# main_board.net
KiCad netlist of a schematic drawn in EasyEDA Pro
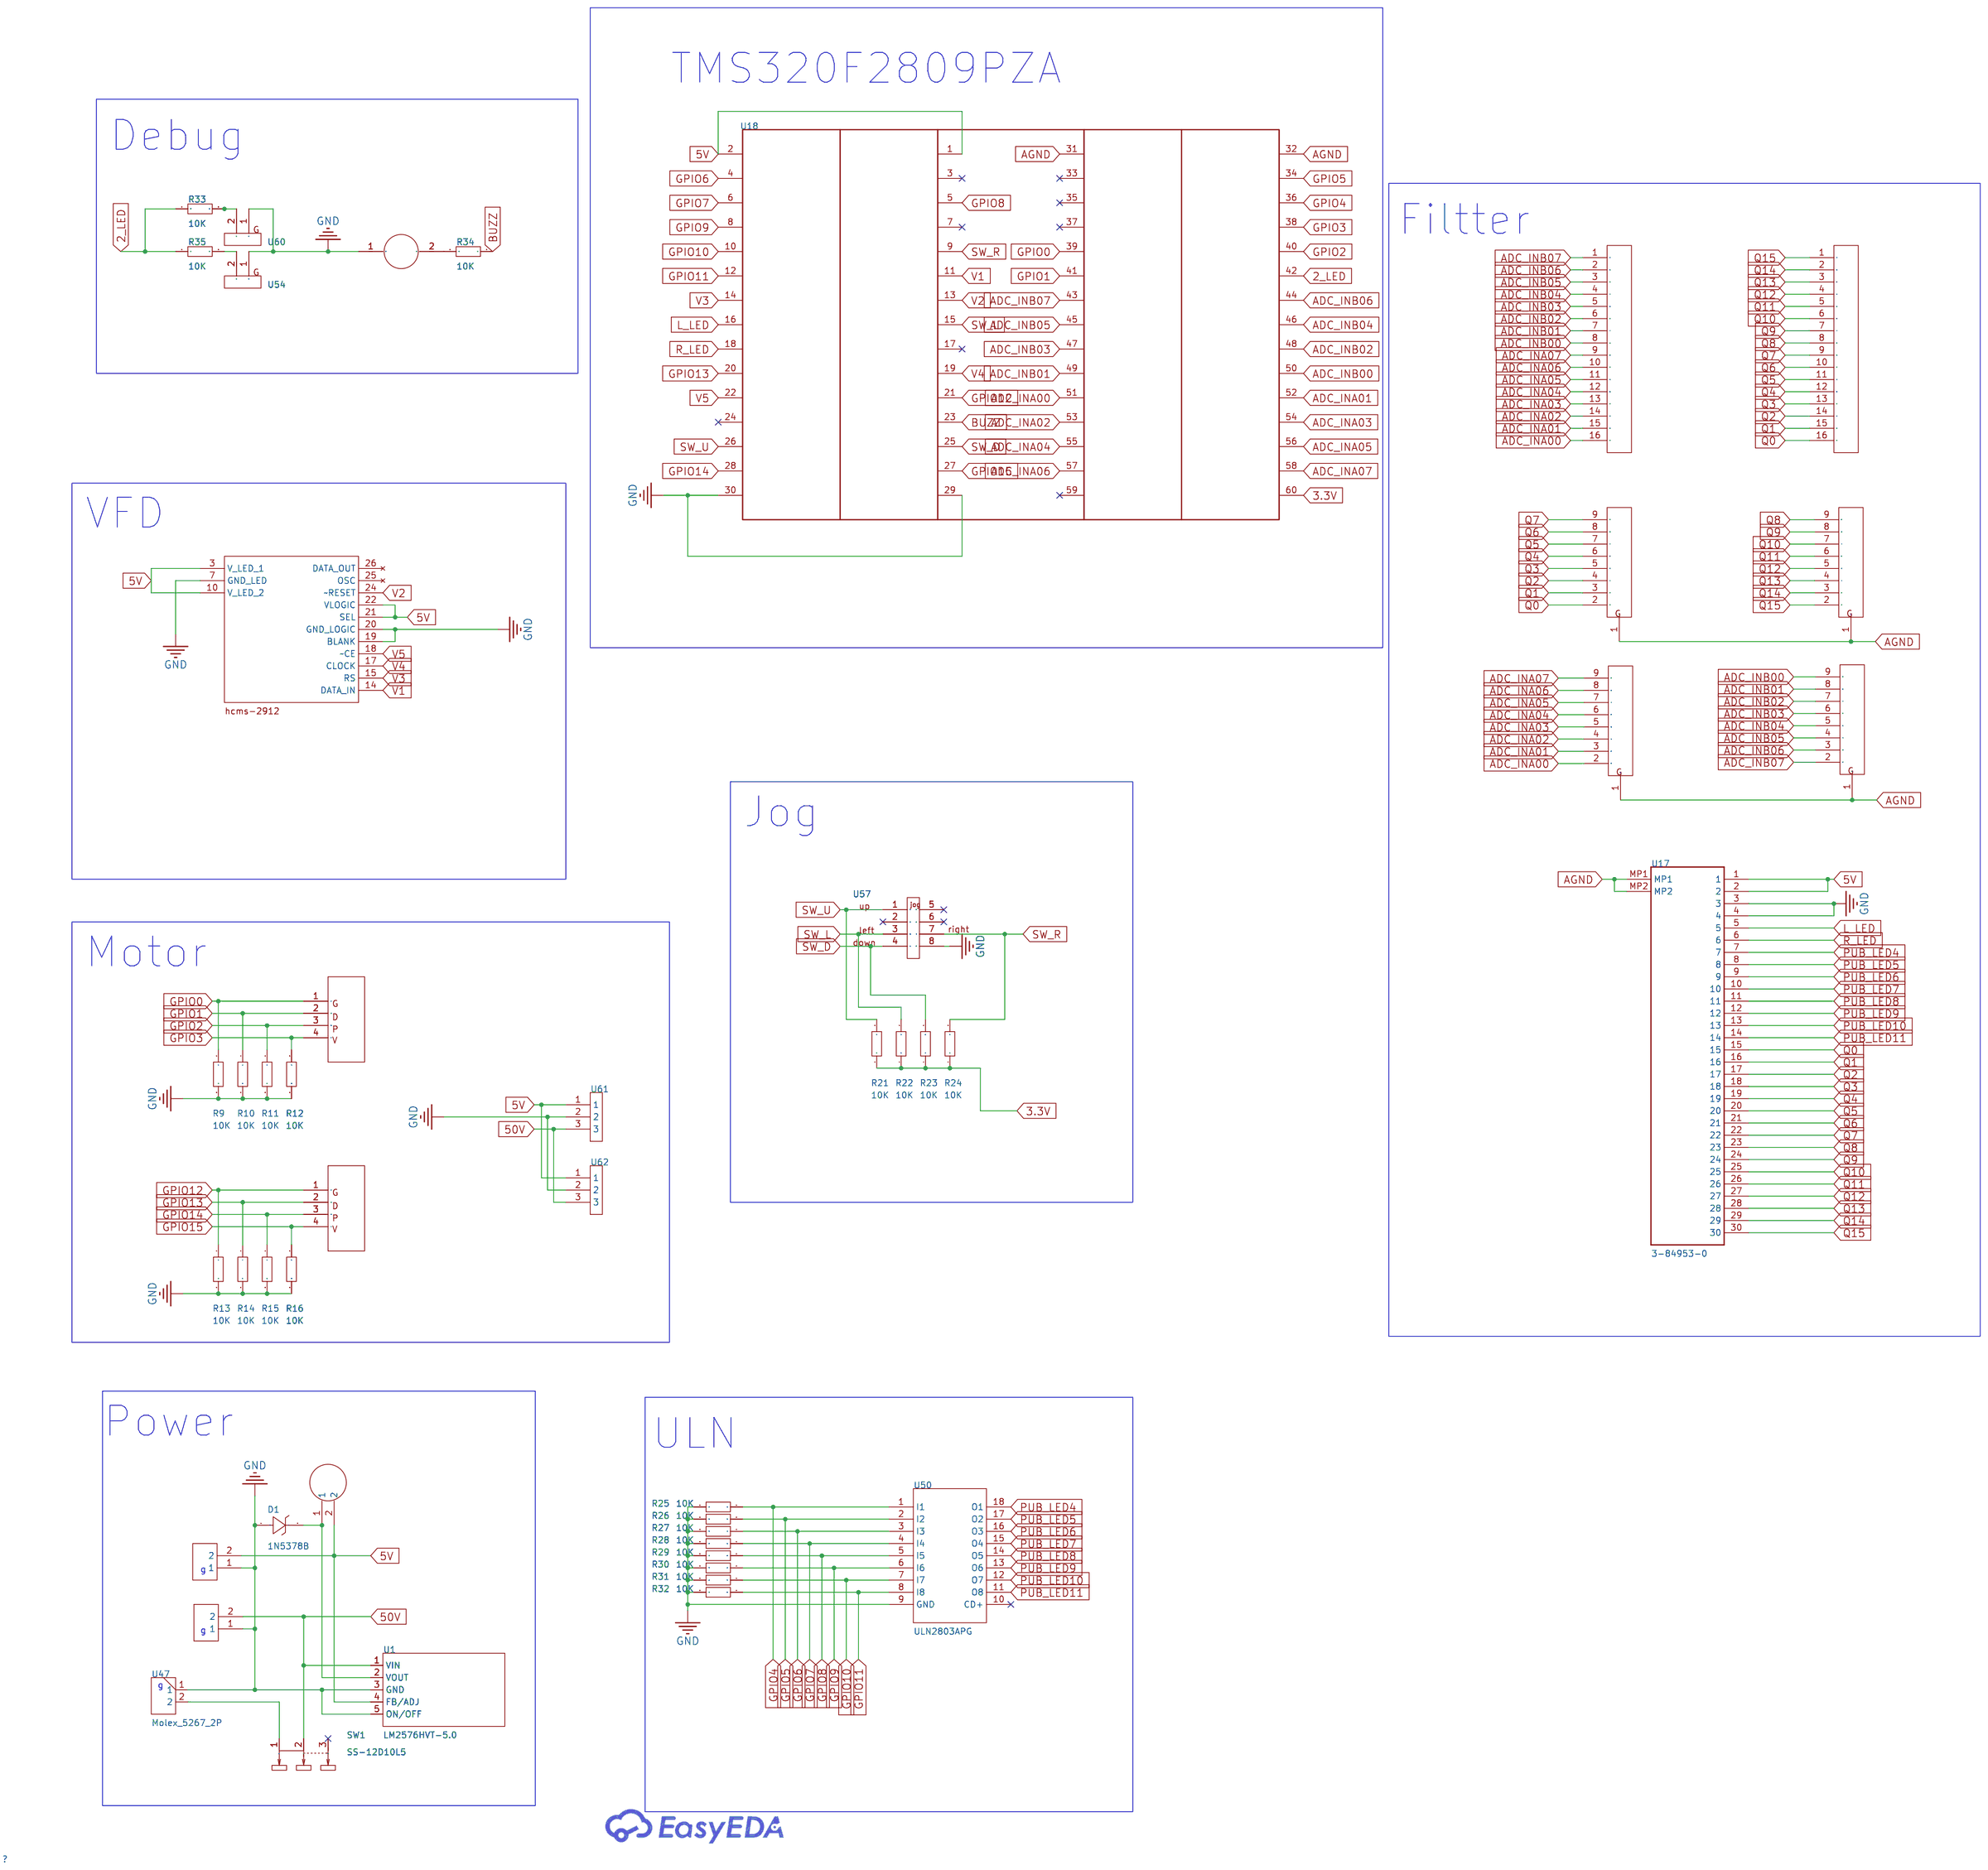
[diagram p0: schematic sheet]

(export (version "E")
  (design (tool "Eeschema 10.0.6"))
  (components
    (comp (ref "C1")
      (value "~")
      (footprint "easyedapro:100uF Capacitor")
      (libsource (lib "easyedapro") (part "100uF Capacitor"))
    )
    (comp (ref "C2")
      (value "~")
      (footprint "easyedapro:1000uF Capacitor")
      (libsource (lib "easyedapro") (part "1000uF Capacitor"))
    )
    (comp (ref "D1")
      (value "1N5378B")
      (footprint "easyedapro:DO-15_BD3.1-L6.7-P10.70-D0.9-FD")
      (fields (field (name "Manufacturer") "EIC"))
      (libsource (lib "easyedapro") (part "1N5378B"))
    )
    (comp (ref "L1")
      (value "~")
      (footprint "easyedapro:Indoctor")
      (libsource (lib "easyedapro") (part "Indoctor"))
    )
    (comp (ref "R9") (value "10K") (footprint "easyedapro:R0603") (libsource (lib "easyedapro") (part "Res")))
    (comp (ref "R10")
      (value "10K")
      (footprint "easyedapro:R0603")
      (libsource (lib "easyedapro") (part "Res"))
    )
    (comp (ref "R11")
      (value "10K")
      (footprint "easyedapro:R0603")
      (libsource (lib "easyedapro") (part "Res"))
    )
    (comp (ref "R12")
      (value "10K")
      (footprint "easyedapro:R0603")
      (libsource (lib "easyedapro") (part "Res"))
    )
    (comp (ref "R13")
      (value "10K")
      (footprint "easyedapro:R0603")
      (libsource (lib "easyedapro") (part "Res"))
    )
    (comp (ref "R14")
      (value "10K")
      (footprint "easyedapro:R0603")
      (libsource (lib "easyedapro") (part "Res"))
    )
    (comp (ref "R15")
      (value "10K")
      (footprint "easyedapro:R0603")
      (libsource (lib "easyedapro") (part "Res"))
    )
    (comp (ref "R16")
      (value "10K")
      (footprint "easyedapro:R0603")
      (libsource (lib "easyedapro") (part "Res"))
    )
    (comp (ref "R21")
      (value "10K")
      (footprint "easyedapro:R0603")
      (libsource (lib "easyedapro") (part "Res"))
    )
    (comp (ref "R22")
      (value "10K")
      (footprint "easyedapro:R0603")
      (libsource (lib "easyedapro") (part "Res"))
    )
    (comp (ref "R23")
      (value "10K")
      (footprint "easyedapro:R0603")
      (libsource (lib "easyedapro") (part "Res"))
    )
    (comp (ref "R24")
      (value "10K")
      (footprint "easyedapro:R0603")
      (libsource (lib "easyedapro") (part "Res"))
    )
    (comp (ref "R25")
      (value "10K")
      (footprint "easyedapro:R0603")
      (libsource (lib "easyedapro") (part "Res"))
    )
    (comp (ref "R26")
      (value "10K")
      (footprint "easyedapro:R0603")
      (libsource (lib "easyedapro") (part "Res"))
    )
    (comp (ref "R27")
      (value "10K")
      (footprint "easyedapro:R0603")
      (libsource (lib "easyedapro") (part "Res"))
    )
    (comp (ref "R28")
      (value "10K")
      (footprint "easyedapro:R0603")
      (libsource (lib "easyedapro") (part "Res"))
    )
    (comp (ref "R29")
      (value "10K")
      (footprint "easyedapro:R0603")
      (libsource (lib "easyedapro") (part "Res"))
    )
    (comp (ref "R30")
      (value "10K")
      (footprint "easyedapro:R0603")
      (libsource (lib "easyedapro") (part "Res"))
    )
    (comp (ref "R31")
      (value "10K")
      (footprint "easyedapro:R0603")
      (libsource (lib "easyedapro") (part "Res"))
    )
    (comp (ref "R32")
      (value "10K")
      (footprint "easyedapro:R0603")
      (libsource (lib "easyedapro") (part "Res"))
    )
    (comp (ref "R33")
      (value "10K")
      (footprint "easyedapro:R0603")
      (libsource (lib "easyedapro") (part "Res"))
    )
    (comp (ref "R34")
      (value "10K")
      (footprint "easyedapro:R0603")
      (libsource (lib "easyedapro") (part "Res"))
    )
    (comp (ref "R35")
      (value "10K")
      (footprint "easyedapro:R0603")
      (libsource (lib "easyedapro") (part "Res"))
    )
    (comp (ref "SW1")
      (value "SS-12D10L5")
      (footprint "easyedapro:SW-TH_SS-12D10L5")
      (fields (field (name "Manufacturer") "XKB Connectivity(中国星坤)"))
      (libsource (lib "easyedapro") (part "SS-12D10L5"))
    )
    (comp (ref "U1")
      (value "LM2576HVT-5.0")
      (footprint "easyedapro:TO-220-5L_L10.2-W4.5-P1.71-L")
      (fields (field (name "Manufacturer") "HTC"))
      (libsource (lib "easyedapro") (part "LM2576HVT-5.0_C262789"))
    )
    (comp (ref "U4")
      (value "Driver_R")
      (footprint "easyedapro:DC_Main_to_Motordriver_Connector_L")
      (libsource (lib "easyedapro") (part "DC_Main_to_Motordriver_Connector"))
    )
    (comp (ref "U6")
      (value "~")
      (footprint "easyedapro:BUZZER")
      (libsource (lib "easyedapro") (part "BUZZER"))
    )
    (comp (ref "U10") (value "~") (libsource (lib "easyedapro") (part "HCMS-2912")))
    (comp (ref "U11")
      (value "~")
      (footprint "easyedapro:Array")
      (libsource (lib "easyedapro") (part "Array"))
    )
    (comp (ref "U12")
      (value "~")
      (footprint "easyedapro:Array")
      (libsource (lib "easyedapro") (part "Array"))
    )
    (comp (ref "U15")
      (value "~")
      (footprint "easyedapro:C_Array")
      (libsource (lib "easyedapro") (part "C_Array"))
    )
    (comp (ref "U16")
      (value "~")
      (footprint "easyedapro:C_Array")
      (libsource (lib "easyedapro") (part "C_Array"))
    )
    (comp (ref "U17")
      (value "3-84953-0")
      (footprint "easyedapro:3849530")
      (libsource (lib "easyedapro") (part "3-84953-0"))
    )
    (comp (ref "U18") (value "~") (libsource (lib "easyedapro") (part "TMS320F2809PZA_DIP")))
    (comp (ref "U47")
      (value "Molex_5267_2P")
      (footprint "easyedapro:5267_2P")
      (libsource (lib "easyedapro") (part "Molex_5267_2P"))
    )
    (comp (ref "U48")
      (value "Driver_L")
      (footprint "easyedapro:DC_Main_to_Motordriver_Connector_L")
      (libsource (lib "easyedapro") (part "DC_Main_to_Motordriver_Connector"))
    )
    (comp (ref "U50")
      (value "ULN2803APG")
      (footprint "easyedapro:DIP-18_L23.0-W6.5-P2.54-LS7.6-BL")
      (description "number of channels:Eight channels")
      (fields (field (name "Manufacturer") "TOSHIBA(东芝)"))
      (libsource (lib "easyedapro") (part "ULN2803APG"))
    )
    (comp (ref "U51")
      (value "~")
      (footprint "easyedapro:Array")
      (libsource (lib "easyedapro") (part "Array"))
    )
    (comp (ref "U52")
      (value "~")
      (footprint "easyedapro:Array")
      (libsource (lib "easyedapro") (part "Array"))
    )
    (comp (ref "U54")
      (value "~")
      (footprint "easyedapro:pub_pin")
      (libsource (lib "easyedapro") (part "pub_pin"))
    )
    (comp (ref "U57") (value "~") (footprint "easyedapro:jog") (libsource (lib "easyedapro") (part "jog")))
    (comp (ref "U60")
      (value "~")
      (footprint "easyedapro:pub_pin")
      (libsource (lib "easyedapro") (part "pub_pin"))
    )
    (comp (ref "U61") (value "~") (footprint "easyedapro:pin") (libsource (lib "easyedapro") (part "3pin")))
    (comp (ref "U62") (value "~") (footprint "easyedapro:pin") (libsource (lib "easyedapro") (part "3pin")))
  )
  (nets
    (net (code "1") (name "2_LED") (class "Default")
      (node (ref "R33") (pin "1") (pinfunction "1_1") (pintype "input"))
      (node (ref "R35") (pin "1") (pinfunction "1_1") (pintype "input"))
      (node (ref "U18") (pin "42") (pintype "unspecified"))
    )
    (net (code "2") (name "3.3V") (class "Default")
      (node (ref "R21") (pin "1") (pinfunction "1_1") (pintype "input"))
      (node (ref "R22") (pin "1") (pinfunction "1_1") (pintype "input"))
      (node (ref "R23") (pin "1") (pinfunction "1_1") (pintype "input"))
      (node (ref "R24") (pin "1") (pinfunction "1_1") (pintype "input"))
      (node (ref "U18") (pin "60") (pintype "unspecified"))
    )
    (net (code "3") (name "5V") (class "Default")
      (node (ref "C2") (pin "2") (pinfunction "2_2") (pintype "input"))
      (node (ref "L1") (pin "2") (pinfunction "2_2") (pintype "input"))
      (node (ref "U1") (pin "4") (pinfunction "FB/ADJ_4") (pintype "unspecified"))
      (node (ref "U10") (pin "10") (pinfunction "V_LED_2_10") (pintype "unspecified"))
      (node (ref "U10") (pin "21") (pinfunction "SEL_21") (pintype "unspecified"))
      (node (ref "U10") (pin "22") (pinfunction "VLOGIC_22") (pintype "unspecified"))
      (node (ref "U10") (pin "3") (pinfunction "V_LED_1_3") (pintype "unspecified"))
      (node (ref "U17") (pin "1") (pinfunction "1_1") (pintype "bidirectional"))
      (node (ref "U17") (pin "2") (pinfunction "2_2") (pintype "bidirectional"))
      (node (ref "U18") (pin "1") (pintype "unspecified"))
      (node (ref "U18") (pin "2") (pintype "unspecified"))
      (node (ref "U61") (pin "1") (pinfunction "1_1") (pintype "input"))
      (node (ref "U62") (pin "1") (pinfunction "1_1") (pintype "input"))
    )
    (net (code "4") (name "50V") (class "Default")
      (node (ref "C1") (pin "2") (pinfunction "2_2") (pintype "input"))
      (node (ref "SW1") (pin "2") (pinfunction "2_2") (pintype "unspecified"))
      (node (ref "U1") (pin "1") (pinfunction "VIN_1") (pintype "unspecified"))
      (node (ref "U61") (pin "3") (pinfunction "3_3") (pintype "input"))
      (node (ref "U62") (pin "3") (pinfunction "3_3") (pintype "input"))
    )
    (net (code "5") (name "ADC_INA00") (class "Default")
      (node (ref "U15") (pin "16") (pinfunction "16_16") (pintype "input"))
      (node (ref "U18") (pin "51") (pintype "unspecified"))
      (node (ref "U51") (pin "2") (pinfunction "2_2") (pintype "input"))
    )
    (net (code "6") (name "ADC_INA01") (class "Default")
      (node (ref "U15") (pin "15") (pinfunction "15_15") (pintype "input"))
      (node (ref "U18") (pin "52") (pintype "unspecified"))
      (node (ref "U51") (pin "3") (pinfunction "3_3") (pintype "input"))
    )
    (net (code "7") (name "ADC_INA02") (class "Default")
      (node (ref "U15") (pin "14") (pinfunction "14_14") (pintype "input"))
      (node (ref "U18") (pin "53") (pintype "unspecified"))
      (node (ref "U51") (pin "4") (pinfunction "4_4") (pintype "input"))
    )
    (net (code "8") (name "ADC_INA03") (class "Default")
      (node (ref "U15") (pin "13") (pinfunction "13_13") (pintype "input"))
      (node (ref "U18") (pin "54") (pintype "unspecified"))
      (node (ref "U51") (pin "5") (pinfunction "5_5") (pintype "input"))
    )
    (net (code "9") (name "ADC_INA04") (class "Default")
      (node (ref "U15") (pin "12") (pinfunction "12_12") (pintype "input"))
      (node (ref "U18") (pin "55") (pintype "unspecified"))
      (node (ref "U51") (pin "6") (pinfunction "6_6") (pintype "input"))
    )
    (net (code "10") (name "ADC_INA05") (class "Default")
      (node (ref "U15") (pin "11") (pinfunction "11_11") (pintype "input"))
      (node (ref "U18") (pin "56") (pintype "unspecified"))
      (node (ref "U51") (pin "7") (pinfunction "7_7") (pintype "input"))
    )
    (net (code "11") (name "ADC_INA06") (class "Default")
      (node (ref "U15") (pin "10") (pinfunction "10_10") (pintype "input"))
      (node (ref "U18") (pin "57") (pintype "unspecified"))
      (node (ref "U51") (pin "8") (pinfunction "8_8") (pintype "input"))
    )
    (net (code "12") (name "ADC_INA07") (class "Default")
      (node (ref "U15") (pin "9") (pinfunction "9_9") (pintype "input"))
      (node (ref "U18") (pin "58") (pintype "unspecified"))
      (node (ref "U51") (pin "9") (pinfunction "9_9") (pintype "input"))
    )
    (net (code "13") (name "ADC_INB00") (class "Default")
      (node (ref "U15") (pin "8") (pinfunction "8_8") (pintype "input"))
      (node (ref "U18") (pin "50") (pintype "unspecified"))
      (node (ref "U52") (pin "9") (pinfunction "9_9") (pintype "input"))
    )
    (net (code "14") (name "ADC_INB01") (class "Default")
      (node (ref "U15") (pin "7") (pinfunction "7_7") (pintype "input"))
      (node (ref "U18") (pin "49") (pintype "unspecified"))
      (node (ref "U52") (pin "8") (pinfunction "8_8") (pintype "input"))
    )
    (net (code "15") (name "ADC_INB02") (class "Default")
      (node (ref "U15") (pin "6") (pinfunction "6_6") (pintype "input"))
      (node (ref "U18") (pin "48") (pintype "unspecified"))
      (node (ref "U52") (pin "7") (pinfunction "7_7") (pintype "input"))
    )
    (net (code "16") (name "ADC_INB03") (class "Default")
      (node (ref "U15") (pin "5") (pinfunction "5_5") (pintype "input"))
      (node (ref "U18") (pin "47") (pintype "unspecified"))
      (node (ref "U52") (pin "6") (pinfunction "6_6") (pintype "input"))
    )
    (net (code "17") (name "ADC_INB04") (class "Default")
      (node (ref "U15") (pin "4") (pinfunction "4_4") (pintype "input"))
      (node (ref "U18") (pin "46") (pintype "unspecified"))
      (node (ref "U52") (pin "5") (pinfunction "5_5") (pintype "input"))
    )
    (net (code "18") (name "ADC_INB05") (class "Default")
      (node (ref "U15") (pin "3") (pinfunction "3_3") (pintype "input"))
      (node (ref "U18") (pin "45") (pintype "unspecified"))
      (node (ref "U52") (pin "4") (pinfunction "4_4") (pintype "input"))
    )
    (net (code "19") (name "ADC_INB06") (class "Default")
      (node (ref "U15") (pin "2") (pinfunction "2_2") (pintype "input"))
      (node (ref "U18") (pin "44") (pintype "unspecified"))
      (node (ref "U52") (pin "3") (pinfunction "3_3") (pintype "input"))
    )
    (net (code "20") (name "ADC_INB07") (class "Default")
      (node (ref "U15") (pin "1") (pinfunction "1_1") (pintype "input"))
      (node (ref "U18") (pin "43") (pintype "unspecified"))
      (node (ref "U52") (pin "2") (pinfunction "2_2") (pintype "input"))
    )
    (net (code "21") (name "AGND") (class "Default")
      (node (ref "U11") (pin "1") (pinfunction "1_1") (pintype "input"))
      (node (ref "U12") (pin "1") (pinfunction "1_1") (pintype "input"))
      (node (ref "U17") (pin "MP1") (pinfunction "MP1_MP1") (pintype "bidirectional"))
      (node (ref "U17") (pin "MP2") (pinfunction "MP2_MP2") (pintype "bidirectional"))
      (node (ref "U18") (pin "31") (pintype "unspecified"))
      (node (ref "U18") (pin "32") (pintype "unspecified"))
      (node (ref "U51") (pin "1") (pinfunction "1_1") (pintype "input"))
      (node (ref "U52") (pin "1") (pinfunction "1_1") (pintype "input"))
    )
    (net (code "22") (name "BUZZ") (class "Default")
      (node (ref "R34") (pin "2") (pinfunction "2_2") (pintype "input"))
      (node (ref "U18") (pin "23") (pintype "unspecified"))
    )
    (net (code "23") (name "GND") (class "Default")
      (node (ref "C1") (pin "1") (pinfunction "1_1") (pintype "input"))
      (node (ref "C2") (pin "1") (pinfunction "1_1") (pintype "input"))
      (node (ref "D1") (pin "1") (pinfunction "+_1") (pintype "unspecified"))
      (node (ref "R10") (pin "2") (pinfunction "2_2") (pintype "input"))
      (node (ref "R11") (pin "2") (pinfunction "2_2") (pintype "input"))
      (node (ref "R12") (pin "2") (pinfunction "2_2") (pintype "input"))
      (node (ref "R13") (pin "2") (pinfunction "2_2") (pintype "input"))
      (node (ref "R14") (pin "2") (pinfunction "2_2") (pintype "input"))
      (node (ref "R15") (pin "2") (pinfunction "2_2") (pintype "input"))
      (node (ref "R16") (pin "2") (pinfunction "2_2") (pintype "input"))
      (node (ref "R25") (pin "2") (pinfunction "2_2") (pintype "input"))
      (node (ref "R26") (pin "2") (pinfunction "2_2") (pintype "input"))
      (node (ref "R27") (pin "2") (pinfunction "2_2") (pintype "input"))
      (node (ref "R28") (pin "2") (pinfunction "2_2") (pintype "input"))
      (node (ref "R29") (pin "2") (pinfunction "2_2") (pintype "input"))
      (node (ref "R30") (pin "2") (pinfunction "2_2") (pintype "input"))
      (node (ref "R31") (pin "2") (pinfunction "2_2") (pintype "input"))
      (node (ref "R32") (pin "2") (pinfunction "2_2") (pintype "input"))
      (node (ref "R9") (pin "2") (pinfunction "2_2") (pintype "input"))
      (node (ref "U1") (pin "3") (pinfunction "GND_3") (pintype "unspecified"))
      (node (ref "U1") (pin "5") (pinfunction "ON/OFF_5") (pintype "unspecified"))
      (node (ref "U10") (pin "19") (pinfunction "BLANK_19") (pintype "unspecified"))
      (node (ref "U10") (pin "20") (pinfunction "GND_LOGIC_20") (pintype "unspecified"))
      (node (ref "U10") (pin "7") (pinfunction "GND_LED_7") (pintype "unspecified"))
      (node (ref "U17") (pin "3") (pinfunction "3_3") (pintype "bidirectional"))
      (node (ref "U17") (pin "4") (pinfunction "4_4") (pintype "bidirectional"))
      (node (ref "U18") (pin "29") (pintype "unspecified"))
      (node (ref "U18") (pin "30") (pintype "unspecified"))
      (node (ref "U47") (pin "1") (pinfunction "1_1") (pintype "unspecified"))
      (node (ref "U50") (pin "9") (pinfunction "GND_9") (pintype "unspecified"))
      (node (ref "U54") (pin "1") (pinfunction "1_1") (pintype "input"))
      (node (ref "U57") (pin "8") (pinfunction "8_8") (pintype "input"))
      (node (ref "U6") (pin "1") (pinfunction "1_1") (pintype "input"))
      (node (ref "U60") (pin "1") (pinfunction "1_1") (pintype "input"))
      (node (ref "U61") (pin "2") (pinfunction "2_2") (pintype "input"))
      (node (ref "U62") (pin "2") (pinfunction "2_2") (pintype "input"))
    )
    (net (code "24") (name "GPIO0") (class "Default")
      (node (ref "R9") (pin "1") (pinfunction "1_1") (pintype "input"))
      (node (ref "U18") (pin "39") (pintype "unspecified"))
      (node (ref "U4") (pin "1") (pinfunction "1_1") (pintype "input"))
    )
    (net (code "25") (name "GPIO1") (class "Default")
      (node (ref "R10") (pin "1") (pinfunction "1_1") (pintype "input"))
      (node (ref "U18") (pin "41") (pintype "unspecified"))
      (node (ref "U4") (pin "2") (pinfunction "2_2") (pintype "input"))
    )
    (net (code "26") (name "GPIO2") (class "Default")
      (node (ref "R11") (pin "1") (pinfunction "1_1") (pintype "input"))
      (node (ref "U18") (pin "40") (pintype "unspecified"))
      (node (ref "U4") (pin "3") (pinfunction "3_3") (pintype "input"))
    )
    (net (code "27") (name "GPIO3") (class "Default")
      (node (ref "R12") (pin "1") (pinfunction "1_1") (pintype "input"))
      (node (ref "U18") (pin "38") (pintype "unspecified"))
      (node (ref "U4") (pin "4") (pinfunction "4_4") (pintype "input"))
    )
    (net (code "28") (name "GPIO4") (class "Default")
      (node (ref "R25") (pin "1") (pinfunction "1_1") (pintype "input"))
      (node (ref "U18") (pin "36") (pintype "unspecified"))
      (node (ref "U50") (pin "1") (pinfunction "I1_1") (pintype "input"))
    )
    (net (code "29") (name "GPIO5") (class "Default")
      (node (ref "R26") (pin "1") (pinfunction "1_1") (pintype "input"))
      (node (ref "U18") (pin "34") (pintype "unspecified"))
      (node (ref "U50") (pin "2") (pinfunction "I2_2") (pintype "input"))
    )
    (net (code "30") (name "GPIO6") (class "Default")
      (node (ref "R27") (pin "1") (pinfunction "1_1") (pintype "input"))
      (node (ref "U18") (pin "4") (pintype "unspecified"))
      (node (ref "U50") (pin "3") (pinfunction "I3_3") (pintype "input"))
    )
    (net (code "31") (name "GPIO7") (class "Default")
      (node (ref "R28") (pin "1") (pinfunction "1_1") (pintype "input"))
      (node (ref "U18") (pin "6") (pintype "unspecified"))
      (node (ref "U50") (pin "4") (pinfunction "I4_4") (pintype "input"))
    )
    (net (code "32") (name "GPIO8") (class "Default")
      (node (ref "R29") (pin "1") (pinfunction "1_1") (pintype "input"))
      (node (ref "U18") (pin "5") (pintype "unspecified"))
      (node (ref "U50") (pin "5") (pinfunction "I5_5") (pintype "input"))
    )
    (net (code "33") (name "GPIO9") (class "Default")
      (node (ref "R30") (pin "1") (pinfunction "1_1") (pintype "input"))
      (node (ref "U18") (pin "8") (pintype "unspecified"))
      (node (ref "U50") (pin "6") (pinfunction "I6_6") (pintype "input"))
    )
    (net (code "34") (name "GPIO10") (class "Default")
      (node (ref "R31") (pin "1") (pinfunction "1_1") (pintype "input"))
      (node (ref "U18") (pin "10") (pintype "unspecified"))
      (node (ref "U50") (pin "7") (pinfunction "I7_7") (pintype "input"))
    )
    (net (code "35") (name "GPIO11") (class "Default")
      (node (ref "R32") (pin "1") (pinfunction "1_1") (pintype "input"))
      (node (ref "U18") (pin "12") (pintype "unspecified"))
      (node (ref "U50") (pin "8") (pinfunction "I8_8") (pintype "input"))
    )
    (net (code "36") (name "GPIO12") (class "Default")
      (node (ref "R13") (pin "1") (pinfunction "1_1") (pintype "input"))
      (node (ref "U18") (pin "21") (pintype "unspecified"))
      (node (ref "U48") (pin "1") (pinfunction "1_1") (pintype "input"))
    )
    (net (code "37") (name "GPIO13") (class "Default")
      (node (ref "R14") (pin "1") (pinfunction "1_1") (pintype "input"))
      (node (ref "U18") (pin "20") (pintype "unspecified"))
      (node (ref "U48") (pin "2") (pinfunction "2_2") (pintype "input"))
    )
    (net (code "38") (name "GPIO14") (class "Default")
      (node (ref "R15") (pin "1") (pinfunction "1_1") (pintype "input"))
      (node (ref "U18") (pin "28") (pintype "unspecified"))
      (node (ref "U48") (pin "3") (pinfunction "3_3") (pintype "input"))
    )
    (net (code "39") (name "GPIO15") (class "Default")
      (node (ref "R16") (pin "1") (pinfunction "1_1") (pintype "input"))
      (node (ref "U18") (pin "27") (pintype "unspecified"))
      (node (ref "U48") (pin "4") (pinfunction "4_4") (pintype "input"))
    )
    (net (code "40") (name "L_LED") (class "Default")
      (node (ref "U17") (pin "5") (pinfunction "5_5") (pintype "bidirectional"))
      (node (ref "U18") (pin "16") (pintype "unspecified"))
    )
    (net (code "41") (name "Net-(D1--)") (class "Default")
      (node (ref "D1") (pin "2") (pinfunction "-_2") (pintype "unspecified"))
      (node (ref "L1") (pin "1") (pinfunction "1_1") (pintype "input"))
      (node (ref "U1") (pin "2") (pinfunction "VOUT_2") (pintype "unspecified"))
    )
    (net (code "42") (name "Net-(R33-Pad2)") (class "Default")
      (node (ref "R33") (pin "2") (pinfunction "2_2") (pintype "input"))
      (node (ref "U60") (pin "2") (pinfunction "2_2") (pintype "input"))
    )
    (net (code "43") (name "Net-(R34-Pad1)") (class "Default")
      (node (ref "R34") (pin "1") (pinfunction "1_1") (pintype "input"))
      (node (ref "U6") (pin "2") (pinfunction "2_2") (pintype "input"))
    )
    (net (code "44") (name "Net-(R35-Pad2)") (class "Default")
      (node (ref "R35") (pin "2") (pinfunction "2_2") (pintype "input"))
      (node (ref "U54") (pin "2") (pinfunction "2_2") (pintype "input"))
    )
    (net (code "45") (name "Net-(SW1-Pad1)") (class "Default")
      (node (ref "SW1") (pin "1") (pinfunction "1_1") (pintype "unspecified"))
      (node (ref "U47") (pin "2") (pinfunction "2_2") (pintype "unspecified"))
    )
    (net (code "46") (name "PUB_LED4") (class "Default")
      (node (ref "U17") (pin "7") (pinfunction "7_7") (pintype "bidirectional"))
      (node (ref "U50") (pin "18") (pinfunction "O1_18") (pintype "unspecified"))
    )
    (net (code "47") (name "PUB_LED5") (class "Default")
      (node (ref "U17") (pin "8") (pinfunction "8_8") (pintype "bidirectional"))
      (node (ref "U50") (pin "17") (pinfunction "O2_17") (pintype "unspecified"))
    )
    (net (code "48") (name "PUB_LED6") (class "Default")
      (node (ref "U17") (pin "9") (pinfunction "9_9") (pintype "bidirectional"))
      (node (ref "U50") (pin "16") (pinfunction "O3_16") (pintype "unspecified"))
    )
    (net (code "49") (name "PUB_LED7") (class "Default")
      (node (ref "U17") (pin "10") (pinfunction "10_10") (pintype "bidirectional"))
      (node (ref "U50") (pin "15") (pinfunction "O4_15") (pintype "unspecified"))
    )
    (net (code "50") (name "PUB_LED8") (class "Default")
      (node (ref "U17") (pin "11") (pinfunction "11_11") (pintype "bidirectional"))
      (node (ref "U50") (pin "14") (pinfunction "O5_14") (pintype "unspecified"))
    )
    (net (code "51") (name "PUB_LED9") (class "Default")
      (node (ref "U17") (pin "12") (pinfunction "12_12") (pintype "bidirectional"))
      (node (ref "U50") (pin "13") (pinfunction "O6_13") (pintype "unspecified"))
    )
    (net (code "52") (name "PUB_LED10") (class "Default")
      (node (ref "U17") (pin "13") (pinfunction "13_13") (pintype "bidirectional"))
      (node (ref "U50") (pin "12") (pinfunction "O7_12") (pintype "unspecified"))
    )
    (net (code "53") (name "PUB_LED11") (class "Default")
      (node (ref "U17") (pin "14") (pinfunction "14_14") (pintype "bidirectional"))
      (node (ref "U50") (pin "11") (pinfunction "O8_11") (pintype "unspecified"))
    )
    (net (code "54") (name "Q0") (class "Default")
      (node (ref "U11") (pin "2") (pinfunction "2_2") (pintype "input"))
      (node (ref "U16") (pin "16") (pinfunction "16_16") (pintype "input"))
      (node (ref "U17") (pin "15") (pinfunction "15_15") (pintype "bidirectional"))
    )
    (net (code "55") (name "Q1") (class "Default")
      (node (ref "U11") (pin "3") (pinfunction "3_3") (pintype "input"))
      (node (ref "U16") (pin "15") (pinfunction "15_15") (pintype "input"))
      (node (ref "U17") (pin "16") (pinfunction "16_16") (pintype "bidirectional"))
    )
    (net (code "56") (name "Q2") (class "Default")
      (node (ref "U11") (pin "4") (pinfunction "4_4") (pintype "input"))
      (node (ref "U16") (pin "14") (pinfunction "14_14") (pintype "input"))
      (node (ref "U17") (pin "17") (pinfunction "17_17") (pintype "bidirectional"))
    )
    (net (code "57") (name "Q3") (class "Default")
      (node (ref "U11") (pin "5") (pinfunction "5_5") (pintype "input"))
      (node (ref "U16") (pin "13") (pinfunction "13_13") (pintype "input"))
      (node (ref "U17") (pin "18") (pinfunction "18_18") (pintype "bidirectional"))
    )
    (net (code "58") (name "Q4") (class "Default")
      (node (ref "U11") (pin "6") (pinfunction "6_6") (pintype "input"))
      (node (ref "U16") (pin "12") (pinfunction "12_12") (pintype "input"))
      (node (ref "U17") (pin "19") (pinfunction "19_19") (pintype "bidirectional"))
    )
    (net (code "59") (name "Q5") (class "Default")
      (node (ref "U11") (pin "7") (pinfunction "7_7") (pintype "input"))
      (node (ref "U16") (pin "11") (pinfunction "11_11") (pintype "input"))
      (node (ref "U17") (pin "20") (pinfunction "20_20") (pintype "bidirectional"))
    )
    (net (code "60") (name "Q6") (class "Default")
      (node (ref "U11") (pin "8") (pinfunction "8_8") (pintype "input"))
      (node (ref "U16") (pin "10") (pinfunction "10_10") (pintype "input"))
      (node (ref "U17") (pin "21") (pinfunction "21_21") (pintype "bidirectional"))
    )
    (net (code "61") (name "Q7") (class "Default")
      (node (ref "U11") (pin "9") (pinfunction "9_9") (pintype "input"))
      (node (ref "U16") (pin "9") (pinfunction "9_9") (pintype "input"))
      (node (ref "U17") (pin "22") (pinfunction "22_22") (pintype "bidirectional"))
    )
    (net (code "62") (name "Q8") (class "Default")
      (node (ref "U12") (pin "9") (pinfunction "9_9") (pintype "input"))
      (node (ref "U16") (pin "8") (pinfunction "8_8") (pintype "input"))
      (node (ref "U17") (pin "23") (pinfunction "23_23") (pintype "bidirectional"))
    )
    (net (code "63") (name "Q9") (class "Default")
      (node (ref "U12") (pin "8") (pinfunction "8_8") (pintype "input"))
      (node (ref "U16") (pin "7") (pinfunction "7_7") (pintype "input"))
      (node (ref "U17") (pin "24") (pinfunction "24_24") (pintype "bidirectional"))
    )
    (net (code "64") (name "Q10") (class "Default")
      (node (ref "U12") (pin "7") (pinfunction "7_7") (pintype "input"))
      (node (ref "U16") (pin "6") (pinfunction "6_6") (pintype "input"))
      (node (ref "U17") (pin "25") (pinfunction "25_25") (pintype "bidirectional"))
    )
    (net (code "65") (name "Q11") (class "Default")
      (node (ref "U12") (pin "6") (pinfunction "6_6") (pintype "input"))
      (node (ref "U16") (pin "5") (pinfunction "5_5") (pintype "input"))
      (node (ref "U17") (pin "26") (pinfunction "26_26") (pintype "bidirectional"))
    )
    (net (code "66") (name "Q12") (class "Default")
      (node (ref "U12") (pin "5") (pinfunction "5_5") (pintype "input"))
      (node (ref "U16") (pin "4") (pinfunction "4_4") (pintype "input"))
      (node (ref "U17") (pin "27") (pinfunction "27_27") (pintype "bidirectional"))
    )
    (net (code "67") (name "Q13") (class "Default")
      (node (ref "U12") (pin "4") (pinfunction "4_4") (pintype "input"))
      (node (ref "U16") (pin "3") (pinfunction "3_3") (pintype "input"))
      (node (ref "U17") (pin "28") (pinfunction "28_28") (pintype "bidirectional"))
    )
    (net (code "68") (name "Q14") (class "Default")
      (node (ref "U12") (pin "3") (pinfunction "3_3") (pintype "input"))
      (node (ref "U16") (pin "2") (pinfunction "2_2") (pintype "input"))
      (node (ref "U17") (pin "29") (pinfunction "29_29") (pintype "bidirectional"))
    )
    (net (code "69") (name "Q15") (class "Default")
      (node (ref "U12") (pin "2") (pinfunction "2_2") (pintype "input"))
      (node (ref "U16") (pin "1") (pinfunction "1_1") (pintype "input"))
      (node (ref "U17") (pin "30") (pinfunction "30_30") (pintype "bidirectional"))
    )
    (net (code "70") (name "R_LED") (class "Default")
      (node (ref "U17") (pin "6") (pinfunction "6_6") (pintype "bidirectional"))
      (node (ref "U18") (pin "18") (pintype "unspecified"))
    )
    (net (code "71") (name "SW_D") (class "Default")
      (node (ref "R23") (pin "2") (pinfunction "2_2") (pintype "input"))
      (node (ref "U18") (pin "25") (pintype "unspecified"))
      (node (ref "U57") (pin "4") (pinfunction "4_4") (pintype "input"))
    )
    (net (code "72") (name "SW_L") (class "Default")
      (node (ref "R22") (pin "2") (pinfunction "2_2") (pintype "input"))
      (node (ref "U18") (pin "15") (pintype "unspecified"))
      (node (ref "U57") (pin "3") (pinfunction "3_3") (pintype "input"))
    )
    (net (code "73") (name "SW_R") (class "Default")
      (node (ref "R24") (pin "2") (pinfunction "2_2") (pintype "input"))
      (node (ref "U18") (pin "9") (pintype "unspecified"))
      (node (ref "U57") (pin "7") (pinfunction "7_7") (pintype "input"))
    )
    (net (code "74") (name "SW_U") (class "Default")
      (node (ref "R21") (pin "2") (pinfunction "2_2") (pintype "input"))
      (node (ref "U18") (pin "26") (pintype "unspecified"))
      (node (ref "U57") (pin "1") (pinfunction "1_1") (pintype "input"))
    )
    (net (code "75") (name "V1") (class "Default")
      (node (ref "U10") (pin "14") (pinfunction "DATA_IN_14") (pintype "unspecified"))
      (node (ref "U18") (pin "11") (pintype "unspecified"))
    )
    (net (code "76") (name "V2") (class "Default")
      (node (ref "U10") (pin "24") (pinfunction "~RESET_24") (pintype "unspecified"))
      (node (ref "U18") (pin "13") (pintype "unspecified"))
    )
    (net (code "77") (name "V3") (class "Default")
      (node (ref "U10") (pin "15") (pinfunction "RS_15") (pintype "unspecified"))
      (node (ref "U18") (pin "14") (pintype "unspecified"))
    )
    (net (code "78") (name "V4") (class "Default")
      (node (ref "U10") (pin "17") (pinfunction "CLOCK_17") (pintype "unspecified"))
      (node (ref "U18") (pin "19") (pintype "unspecified"))
    )
    (net (code "79") (name "V5") (class "Default")
      (node (ref "U10") (pin "18") (pinfunction "~CE_18") (pintype "unspecified"))
      (node (ref "U18") (pin "22") (pintype "unspecified"))
    )
    (net (code "80") (name "unconnected-(SW1-Pad3)") (class "Default")
      (node (ref "SW1") (pin "3") (pinfunction "3_3") (pintype "unspecified+no_connect"))
    )
    (net (code "81") (name "unconnected-(U10-DATA_OUT-Pad26)") (class "Default")
      (node (ref "U10") (pin "26") (pinfunction "DATA_OUT_26") (pintype "no_connect"))
    )
    (net (code "82") (name "unconnected-(U10-OSC-Pad25)") (class "Default")
      (node (ref "U10") (pin "25") (pinfunction "OSC_25") (pintype "no_connect"))
    )
    (net (code "83") (name "unconnected-(U18-Pad3)") (class "Default")
      (node (ref "U18") (pin "3") (pintype "unspecified+no_connect"))
    )
    (net (code "84") (name "unconnected-(U18-Pad7)") (class "Default")
      (node (ref "U18") (pin "7") (pintype "unspecified+no_connect"))
    )
    (net (code "85") (name "unconnected-(U18-Pad17)") (class "Default")
      (node (ref "U18") (pin "17") (pintype "unspecified+no_connect"))
    )
    (net (code "86") (name "unconnected-(U18-Pad24)") (class "Default")
      (node (ref "U18") (pin "24") (pintype "unspecified+no_connect"))
    )
    (net (code "87") (name "unconnected-(U18-Pad33)") (class "Default")
      (node (ref "U18") (pin "33") (pintype "unspecified+no_connect"))
    )
    (net (code "88") (name "unconnected-(U18-Pad35)") (class "Default")
      (node (ref "U18") (pin "35") (pintype "unspecified+no_connect"))
    )
    (net (code "89") (name "unconnected-(U18-Pad37)") (class "Default")
      (node (ref "U18") (pin "37") (pintype "unspecified+no_connect"))
    )
    (net (code "90") (name "unconnected-(U18-Pad59)") (class "Default")
      (node (ref "U18") (pin "59") (pintype "unspecified+no_connect"))
    )
    (net (code "91") (name "unconnected-(U50-CD+-Pad10)") (class "Default")
      (node (ref "U50") (pin "10") (pinfunction "CD+_10") (pintype "unspecified+no_connect"))
    )
    (net (code "92") (name "unconnected-(U57-Pad2)") (class "Default")
      (node (ref "U57") (pin "2") (pinfunction "2_2") (pintype "input+no_connect"))
    )
    (net (code "93") (name "unconnected-(U57-Pad5)") (class "Default")
      (node (ref "U57") (pin "5") (pinfunction "5_5") (pintype "input+no_connect"))
    )
    (net (code "94") (name "unconnected-(U57-Pad6)") (class "Default")
      (node (ref "U57") (pin "6") (pinfunction "6_6") (pintype "input+no_connect"))
    )
  )
)
